# 20inputAND.net
KiCad netlist of a schematic drawn in EAGLE
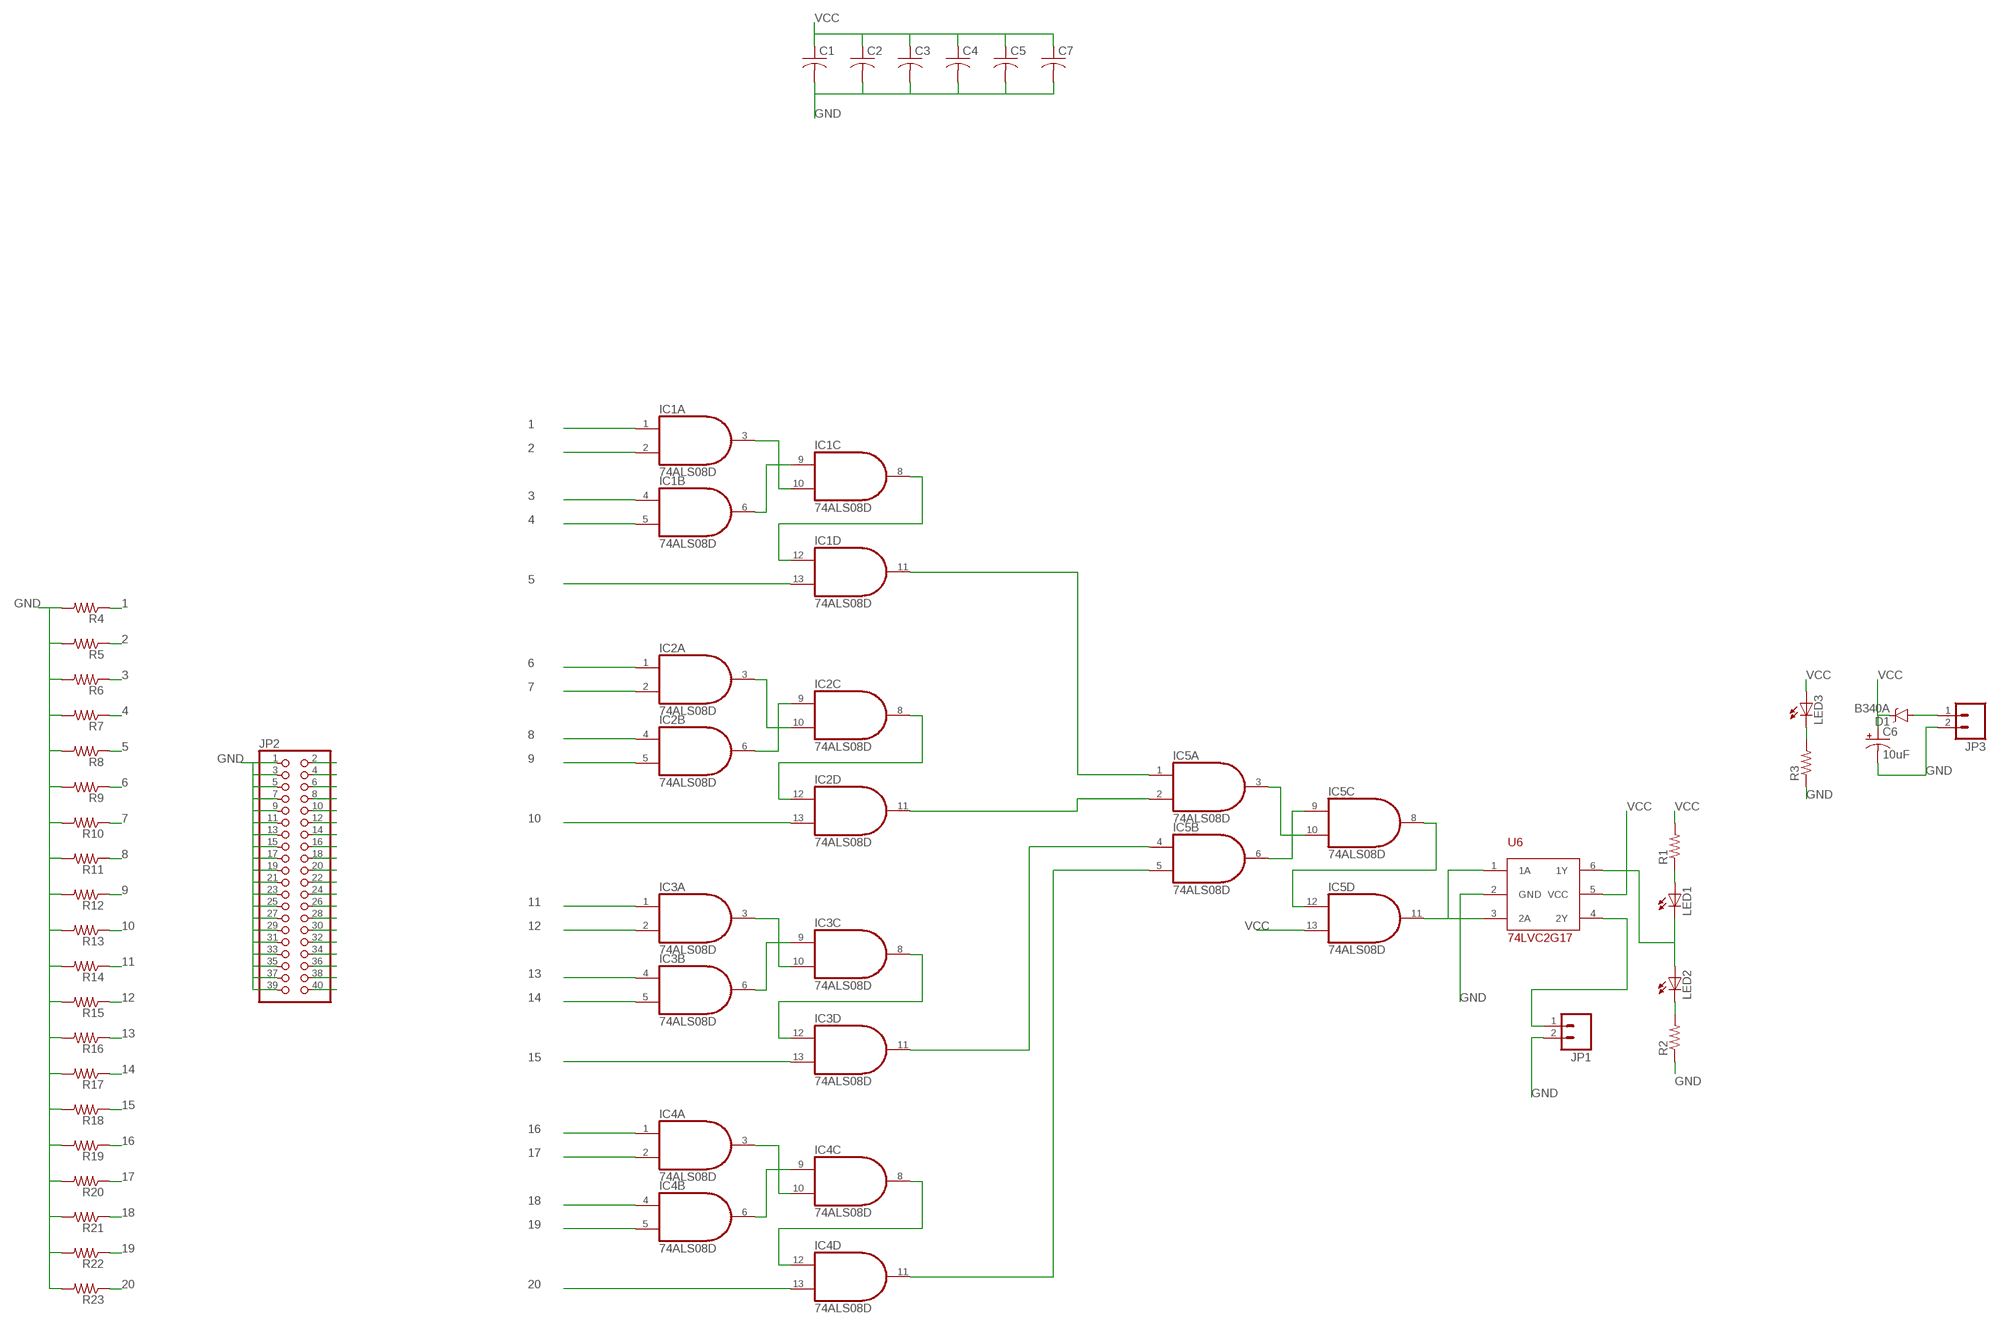
[diagram p0: schematic, sheet 1]

(export (version "E")
  (design (tool "Eeschema 10.0.6"))
  (components
    (comp (ref "C1")
      (value "C-USC0603")
      (footprint "eagle-import:C0603")
      (libsource (lib "eagle-import") (part "C-USC0603"))
    )
    (comp (ref "C2")
      (value "C-USC0603")
      (footprint "eagle-import:C0603")
      (libsource (lib "eagle-import") (part "C-USC0603"))
    )
    (comp (ref "C3")
      (value "C-USC0603")
      (footprint "eagle-import:C0603")
      (libsource (lib "eagle-import") (part "C-USC0603"))
    )
    (comp (ref "C4")
      (value "C-USC0603")
      (footprint "eagle-import:C0603")
      (libsource (lib "eagle-import") (part "C-USC0603"))
    )
    (comp (ref "C5")
      (value "C-USC0603")
      (footprint "eagle-import:C0603")
      (libsource (lib "eagle-import") (part "C-USC0603"))
    )
    (comp (ref "C6")
      (value "10uF")
      (footprint "eagle-import:EIA3216")
      (libsource (lib "eagle-import") (part "10UF-16V-10%(TANT)"))
    )
    (comp (ref "C7")
      (value "C-USC0603")
      (footprint "eagle-import:C0603")
      (libsource (lib "eagle-import") (part "C-USC0603"))
    )
    (comp (ref "D1")
      (value "B340A")
      (footprint "eagle-import:SMA-DIODE")
      (libsource (lib "eagle-import") (part "DIODE-SCHOTTKY-B340A"))
    )
    (comp (ref "IC1")
      (value "74ALS08D")
      (footprint "eagle-import:SO14")
      (libsource (lib "eagle-import") (part "7408DALS"))
    )
    (comp (ref "IC2")
      (value "74ALS08D")
      (footprint "eagle-import:SO14")
      (libsource (lib "eagle-import") (part "7408DALS"))
    )
    (comp (ref "IC3")
      (value "74ALS08D")
      (footprint "eagle-import:SO14")
      (libsource (lib "eagle-import") (part "7408DALS"))
    )
    (comp (ref "IC4")
      (value "74ALS08D")
      (footprint "eagle-import:SO14")
      (libsource (lib "eagle-import") (part "7408DALS"))
    )
    (comp (ref "IC5")
      (value "74ALS08D")
      (footprint "eagle-import:SO14")
      (libsource (lib "eagle-import") (part "7408DALS"))
    )
    (comp (ref "JP1")
      (value "M02PTH")
      (footprint "eagle-import:1X02")
      (libsource (lib "eagle-import") (part "M02PTH"))
    )
    (comp (ref "JP2")
      (value "PINHD-2X20")
      (footprint "eagle-import:2X20")
      (libsource (lib "eagle-import") (part "PINHD-2X20"))
    )
    (comp (ref "JP3")
      (value "M02PTH")
      (footprint "eagle-import:1X02")
      (libsource (lib "eagle-import") (part "M02PTH"))
    )
    (comp (ref "LED1")
      (value "LEDCHIPLED_1206")
      (footprint "eagle-import:CHIPLED_1206")
      (libsource (lib "eagle-import") (part "LEDCHIPLED_1206"))
    )
    (comp (ref "LED2")
      (value "LEDCHIPLED_1206")
      (footprint "eagle-import:CHIPLED_1206")
      (libsource (lib "eagle-import") (part "LEDCHIPLED_1206"))
    )
    (comp (ref "LED3")
      (value "LEDCHIPLED_0805")
      (footprint "eagle-import:CHIPLED_0805")
      (libsource (lib "eagle-import") (part "LEDCHIPLED_0805"))
    )
    (comp (ref "R1")
      (value "R-US_R0603")
      (footprint "eagle-import:R0603")
      (libsource (lib "eagle-import") (part "R-US_R0603"))
    )
    (comp (ref "R2")
      (value "R-US_R0603")
      (footprint "eagle-import:R0603")
      (libsource (lib "eagle-import") (part "R-US_R0603"))
    )
    (comp (ref "R3")
      (value "R-US_R0603")
      (footprint "eagle-import:R0603")
      (libsource (lib "eagle-import") (part "R-US_R0603"))
    )
    (comp (ref "R4")
      (value "R-US_R0603")
      (footprint "eagle-import:R0603")
      (libsource (lib "eagle-import") (part "R-US_R0603"))
    )
    (comp (ref "R5")
      (value "R-US_R0603")
      (footprint "eagle-import:R0603")
      (libsource (lib "eagle-import") (part "R-US_R0603"))
    )
    (comp (ref "R6")
      (value "R-US_R0603")
      (footprint "eagle-import:R0603")
      (libsource (lib "eagle-import") (part "R-US_R0603"))
    )
    (comp (ref "R7")
      (value "R-US_R0603")
      (footprint "eagle-import:R0603")
      (libsource (lib "eagle-import") (part "R-US_R0603"))
    )
    (comp (ref "R8")
      (value "R-US_R0603")
      (footprint "eagle-import:R0603")
      (libsource (lib "eagle-import") (part "R-US_R0603"))
    )
    (comp (ref "R9")
      (value "R-US_R0603")
      (footprint "eagle-import:R0603")
      (libsource (lib "eagle-import") (part "R-US_R0603"))
    )
    (comp (ref "R10")
      (value "R-US_R0603")
      (footprint "eagle-import:R0603")
      (libsource (lib "eagle-import") (part "R-US_R0603"))
    )
    (comp (ref "R11")
      (value "R-US_R0603")
      (footprint "eagle-import:R0603")
      (libsource (lib "eagle-import") (part "R-US_R0603"))
    )
    (comp (ref "R12")
      (value "R-US_R0603")
      (footprint "eagle-import:R0603")
      (libsource (lib "eagle-import") (part "R-US_R0603"))
    )
    (comp (ref "R13")
      (value "R-US_R0603")
      (footprint "eagle-import:R0603")
      (libsource (lib "eagle-import") (part "R-US_R0603"))
    )
    (comp (ref "R14")
      (value "R-US_R0603")
      (footprint "eagle-import:R0603")
      (libsource (lib "eagle-import") (part "R-US_R0603"))
    )
    (comp (ref "R15")
      (value "R-US_R0603")
      (footprint "eagle-import:R0603")
      (libsource (lib "eagle-import") (part "R-US_R0603"))
    )
    (comp (ref "R16")
      (value "R-US_R0603")
      (footprint "eagle-import:R0603")
      (libsource (lib "eagle-import") (part "R-US_R0603"))
    )
    (comp (ref "R17")
      (value "R-US_R0603")
      (footprint "eagle-import:R0603")
      (libsource (lib "eagle-import") (part "R-US_R0603"))
    )
    (comp (ref "R18")
      (value "R-US_R0603")
      (footprint "eagle-import:R0603")
      (libsource (lib "eagle-import") (part "R-US_R0603"))
    )
    (comp (ref "R19")
      (value "R-US_R0603")
      (footprint "eagle-import:R0603")
      (libsource (lib "eagle-import") (part "R-US_R0603"))
    )
    (comp (ref "R20")
      (value "R-US_R0603")
      (footprint "eagle-import:R0603")
      (libsource (lib "eagle-import") (part "R-US_R0603"))
    )
    (comp (ref "R21")
      (value "R-US_R0603")
      (footprint "eagle-import:R0603")
      (libsource (lib "eagle-import") (part "R-US_R0603"))
    )
    (comp (ref "R22")
      (value "R-US_R0603")
      (footprint "eagle-import:R0603")
      (libsource (lib "eagle-import") (part "R-US_R0603"))
    )
    (comp (ref "R23")
      (value "R-US_R0603")
      (footprint "eagle-import:R0603")
      (libsource (lib "eagle-import") (part "R-US_R0603"))
    )
    (comp (ref "U$2")
      (value "74LVC2G14/7")
      (footprint "eagle-import:SOT23-6")
      (libsource (lib "eagle-import") (part "74LVC2G14/7"))
    )
  )
  (nets
    (net (code "1") (name "/1") (class "Default")
      (node (ref "IC1") (pin "1") (pinfunction "I0_1") (pintype "input"))
      (node (ref "JP2") (pin "2") (pinfunction "2_2") (pintype "passive"))
      (node (ref "R4") (pin "1") (pinfunction "1_1") (pintype "passive"))
    )
    (net (code "2") (name "/2") (class "Default")
      (node (ref "IC1") (pin "2") (pinfunction "I1_2") (pintype "input"))
      (node (ref "JP2") (pin "4") (pinfunction "4_4") (pintype "passive"))
      (node (ref "R5") (pin "1") (pinfunction "1_1") (pintype "passive"))
    )
    (net (code "3") (name "/3") (class "Default")
      (node (ref "IC1") (pin "4") (pinfunction "I0_4") (pintype "input"))
      (node (ref "JP2") (pin "6") (pinfunction "6_6") (pintype "passive"))
      (node (ref "R6") (pin "1") (pinfunction "1_1") (pintype "passive"))
    )
    (net (code "4") (name "/4") (class "Default")
      (node (ref "IC1") (pin "5") (pinfunction "I1_5") (pintype "input"))
      (node (ref "JP2") (pin "8") (pinfunction "8_8") (pintype "passive"))
      (node (ref "R7") (pin "1") (pinfunction "1_1") (pintype "passive"))
    )
    (net (code "5") (name "/5") (class "Default")
      (node (ref "IC1") (pin "13") (pinfunction "I1_13") (pintype "input"))
      (node (ref "JP2") (pin "10") (pinfunction "10_10") (pintype "passive"))
      (node (ref "R8") (pin "1") (pinfunction "1_1") (pintype "passive"))
    )
    (net (code "6") (name "/6") (class "Default")
      (node (ref "IC2") (pin "1") (pinfunction "I0_1") (pintype "input"))
      (node (ref "JP2") (pin "12") (pinfunction "12_12") (pintype "passive"))
      (node (ref "R9") (pin "1") (pinfunction "1_1") (pintype "passive"))
    )
    (net (code "7") (name "/7") (class "Default")
      (node (ref "IC2") (pin "2") (pinfunction "I1_2") (pintype "input"))
      (node (ref "JP2") (pin "14") (pinfunction "14_14") (pintype "passive"))
      (node (ref "R10") (pin "1") (pinfunction "1_1") (pintype "passive"))
    )
    (net (code "8") (name "/8") (class "Default")
      (node (ref "IC2") (pin "4") (pinfunction "I0_4") (pintype "input"))
      (node (ref "JP2") (pin "16") (pinfunction "16_16") (pintype "passive"))
      (node (ref "R11") (pin "1") (pinfunction "1_1") (pintype "passive"))
    )
    (net (code "9") (name "/9") (class "Default")
      (node (ref "IC2") (pin "5") (pinfunction "I1_5") (pintype "input"))
      (node (ref "JP2") (pin "18") (pinfunction "18_18") (pintype "passive"))
      (node (ref "R12") (pin "1") (pinfunction "1_1") (pintype "passive"))
    )
    (net (code "10") (name "/10") (class "Default")
      (node (ref "IC2") (pin "13") (pinfunction "I1_13") (pintype "input"))
      (node (ref "JP2") (pin "20") (pinfunction "20_20") (pintype "passive"))
      (node (ref "R13") (pin "1") (pinfunction "1_1") (pintype "passive"))
    )
    (net (code "11") (name "/11") (class "Default")
      (node (ref "IC3") (pin "1") (pinfunction "I0_1") (pintype "input"))
      (node (ref "JP2") (pin "22") (pinfunction "22_22") (pintype "passive"))
      (node (ref "R14") (pin "1") (pinfunction "1_1") (pintype "passive"))
    )
    (net (code "12") (name "/12") (class "Default")
      (node (ref "IC3") (pin "2") (pinfunction "I1_2") (pintype "input"))
      (node (ref "JP2") (pin "24") (pinfunction "24_24") (pintype "passive"))
      (node (ref "R15") (pin "1") (pinfunction "1_1") (pintype "passive"))
    )
    (net (code "13") (name "/13") (class "Default")
      (node (ref "IC3") (pin "4") (pinfunction "I0_4") (pintype "input"))
      (node (ref "JP2") (pin "26") (pinfunction "26_26") (pintype "passive"))
      (node (ref "R16") (pin "1") (pinfunction "1_1") (pintype "passive"))
    )
    (net (code "14") (name "/14") (class "Default")
      (node (ref "IC3") (pin "5") (pinfunction "I1_5") (pintype "input"))
      (node (ref "JP2") (pin "28") (pinfunction "28_28") (pintype "passive"))
      (node (ref "R17") (pin "1") (pinfunction "1_1") (pintype "passive"))
    )
    (net (code "15") (name "/15") (class "Default")
      (node (ref "IC3") (pin "13") (pinfunction "I1_13") (pintype "input"))
      (node (ref "JP2") (pin "30") (pinfunction "30_30") (pintype "passive"))
      (node (ref "R18") (pin "1") (pinfunction "1_1") (pintype "passive"))
    )
    (net (code "16") (name "/16") (class "Default")
      (node (ref "IC4") (pin "1") (pinfunction "I0_1") (pintype "input"))
      (node (ref "JP2") (pin "32") (pinfunction "32_32") (pintype "passive"))
      (node (ref "R19") (pin "1") (pinfunction "1_1") (pintype "passive"))
    )
    (net (code "17") (name "/17") (class "Default")
      (node (ref "IC4") (pin "2") (pinfunction "I1_2") (pintype "input"))
      (node (ref "JP2") (pin "34") (pinfunction "34_34") (pintype "passive"))
      (node (ref "R20") (pin "1") (pinfunction "1_1") (pintype "passive"))
    )
    (net (code "18") (name "/18") (class "Default")
      (node (ref "IC4") (pin "4") (pinfunction "I0_4") (pintype "input"))
      (node (ref "JP2") (pin "36") (pinfunction "36_36") (pintype "passive"))
      (node (ref "R21") (pin "1") (pinfunction "1_1") (pintype "passive"))
    )
    (net (code "19") (name "/19") (class "Default")
      (node (ref "IC4") (pin "5") (pinfunction "I1_5") (pintype "input"))
      (node (ref "JP2") (pin "38") (pinfunction "38_38") (pintype "passive"))
      (node (ref "R22") (pin "1") (pinfunction "1_1") (pintype "passive"))
    )
    (net (code "20") (name "/20") (class "Default")
      (node (ref "IC4") (pin "13") (pinfunction "I1_13") (pintype "input"))
      (node (ref "JP2") (pin "40") (pinfunction "40_40") (pintype "passive"))
      (node (ref "R23") (pin "1") (pinfunction "1_1") (pintype "passive"))
    )
    (net (code "21") (name "/GND") (class "Default")
      (node (ref "C1") (pin "2") (pinfunction "2_2") (pintype "passive"))
      (node (ref "C2") (pin "2") (pinfunction "2_2") (pintype "passive"))
      (node (ref "C3") (pin "2") (pinfunction "2_2") (pintype "passive"))
      (node (ref "C4") (pin "2") (pinfunction "2_2") (pintype "passive"))
      (node (ref "C5") (pin "2") (pinfunction "2_2") (pintype "passive"))
      (node (ref "C6") (pin "C") (pinfunction "-_C") (pintype "passive"))
      (node (ref "C7") (pin "2") (pinfunction "2_2") (pintype "passive"))
      (node (ref "JP1") (pin "2") (pinfunction "2_2") (pintype "passive"))
      (node (ref "JP2") (pin "1") (pinfunction "1_1") (pintype "passive"))
      (node (ref "JP2") (pin "11") (pinfunction "11_11") (pintype "passive"))
      (node (ref "JP2") (pin "13") (pinfunction "13_13") (pintype "passive"))
      (node (ref "JP2") (pin "15") (pinfunction "15_15") (pintype "passive"))
      (node (ref "JP2") (pin "17") (pinfunction "17_17") (pintype "passive"))
      (node (ref "JP2") (pin "19") (pinfunction "19_19") (pintype "passive"))
      (node (ref "JP2") (pin "21") (pinfunction "21_21") (pintype "passive"))
      (node (ref "JP2") (pin "23") (pinfunction "23_23") (pintype "passive"))
      (node (ref "JP2") (pin "25") (pinfunction "25_25") (pintype "passive"))
      (node (ref "JP2") (pin "27") (pinfunction "27_27") (pintype "passive"))
      (node (ref "JP2") (pin "29") (pinfunction "29_29") (pintype "passive"))
      (node (ref "JP2") (pin "3") (pinfunction "3_3") (pintype "passive"))
      (node (ref "JP2") (pin "31") (pinfunction "31_31") (pintype "passive"))
      (node (ref "JP2") (pin "33") (pinfunction "33_33") (pintype "passive"))
      (node (ref "JP2") (pin "35") (pinfunction "35_35") (pintype "passive"))
      (node (ref "JP2") (pin "37") (pinfunction "37_37") (pintype "passive"))
      (node (ref "JP2") (pin "39") (pinfunction "39_39") (pintype "passive"))
      (node (ref "JP2") (pin "5") (pinfunction "5_5") (pintype "passive"))
      (node (ref "JP2") (pin "7") (pinfunction "7_7") (pintype "passive"))
      (node (ref "JP2") (pin "9") (pinfunction "9_9") (pintype "passive"))
      (node (ref "JP3") (pin "2") (pinfunction "2_2") (pintype "passive"))
      (node (ref "R10") (pin "2") (pinfunction "2_2") (pintype "passive"))
      (node (ref "R11") (pin "2") (pinfunction "2_2") (pintype "passive"))
      (node (ref "R12") (pin "2") (pinfunction "2_2") (pintype "passive"))
      (node (ref "R13") (pin "2") (pinfunction "2_2") (pintype "passive"))
      (node (ref "R14") (pin "2") (pinfunction "2_2") (pintype "passive"))
      (node (ref "R15") (pin "2") (pinfunction "2_2") (pintype "passive"))
      (node (ref "R16") (pin "2") (pinfunction "2_2") (pintype "passive"))
      (node (ref "R17") (pin "2") (pinfunction "2_2") (pintype "passive"))
      (node (ref "R18") (pin "2") (pinfunction "2_2") (pintype "passive"))
      (node (ref "R19") (pin "2") (pinfunction "2_2") (pintype "passive"))
      (node (ref "R2") (pin "1") (pinfunction "1_1") (pintype "passive"))
      (node (ref "R20") (pin "2") (pinfunction "2_2") (pintype "passive"))
      (node (ref "R21") (pin "2") (pinfunction "2_2") (pintype "passive"))
      (node (ref "R22") (pin "2") (pinfunction "2_2") (pintype "passive"))
      (node (ref "R23") (pin "2") (pinfunction "2_2") (pintype "passive"))
      (node (ref "R3") (pin "1") (pinfunction "1_1") (pintype "passive"))
      (node (ref "R4") (pin "2") (pinfunction "2_2") (pintype "passive"))
      (node (ref "R5") (pin "2") (pinfunction "2_2") (pintype "passive"))
      (node (ref "R6") (pin "2") (pinfunction "2_2") (pintype "passive"))
      (node (ref "R7") (pin "2") (pinfunction "2_2") (pintype "passive"))
      (node (ref "R8") (pin "2") (pinfunction "2_2") (pintype "passive"))
      (node (ref "R9") (pin "2") (pinfunction "2_2") (pintype "passive"))
      (node (ref "U$2") (pin "2") (pinfunction "GND_2") (pintype "bidirectional"))
    )
    (net (code "22") (name "/VCC") (class "Default")
      (node (ref "C1") (pin "1") (pinfunction "1_1") (pintype "passive"))
      (node (ref "C2") (pin "1") (pinfunction "1_1") (pintype "passive"))
      (node (ref "C3") (pin "1") (pinfunction "1_1") (pintype "passive"))
      (node (ref "C4") (pin "1") (pinfunction "1_1") (pintype "passive"))
      (node (ref "C5") (pin "1") (pinfunction "1_1") (pintype "passive"))
      (node (ref "C6") (pin "A") (pinfunction "+_A") (pintype "passive"))
      (node (ref "C7") (pin "1") (pinfunction "1_1") (pintype "passive"))
      (node (ref "D1") (pin "C") (pinfunction "C_C") (pintype "passive"))
      (node (ref "IC5") (pin "13") (pinfunction "I1_13") (pintype "input"))
      (node (ref "LED3") (pin "A") (pinfunction "A_A") (pintype "passive"))
      (node (ref "R1") (pin "2") (pinfunction "2_2") (pintype "passive"))
      (node (ref "U$2") (pin "5") (pinfunction "VCC_5") (pintype "bidirectional"))
    )
    (net (code "23") (name "Net-(D1-PadA)") (class "Default")
      (node (ref "D1") (pin "A") (pinfunction "A_A") (pintype "passive"))
      (node (ref "JP3") (pin "1") (pinfunction "1_1") (pintype "passive"))
    )
    (net (code "24") (name "Net-(IC1A-O)") (class "Default")
      (node (ref "IC1") (pin "10") (pinfunction "I1_10") (pintype "input"))
      (node (ref "IC1") (pin "3") (pinfunction "O_3") (pintype "output"))
    )
    (net (code "25") (name "Net-(IC1B-O)") (class "Default")
      (node (ref "IC1") (pin "6") (pinfunction "O_6") (pintype "output"))
      (node (ref "IC1") (pin "9") (pinfunction "I0_9") (pintype "input"))
    )
    (net (code "26") (name "Net-(IC1C-O)") (class "Default")
      (node (ref "IC1") (pin "12") (pinfunction "I0_12") (pintype "input"))
      (node (ref "IC1") (pin "8") (pinfunction "O_8") (pintype "output"))
    )
    (net (code "27") (name "Net-(IC1D-O)") (class "Default")
      (node (ref "IC1") (pin "11") (pinfunction "O_11") (pintype "output"))
      (node (ref "IC5") (pin "1") (pinfunction "I0_1") (pintype "input"))
    )
    (net (code "28") (name "Net-(IC2A-O)") (class "Default")
      (node (ref "IC2") (pin "10") (pinfunction "I1_10") (pintype "input"))
      (node (ref "IC2") (pin "3") (pinfunction "O_3") (pintype "output"))
    )
    (net (code "29") (name "Net-(IC2B-O)") (class "Default")
      (node (ref "IC2") (pin "6") (pinfunction "O_6") (pintype "output"))
      (node (ref "IC2") (pin "9") (pinfunction "I0_9") (pintype "input"))
    )
    (net (code "30") (name "Net-(IC2C-O)") (class "Default")
      (node (ref "IC2") (pin "12") (pinfunction "I0_12") (pintype "input"))
      (node (ref "IC2") (pin "8") (pinfunction "O_8") (pintype "output"))
    )
    (net (code "31") (name "Net-(IC2D-O)") (class "Default")
      (node (ref "IC2") (pin "11") (pinfunction "O_11") (pintype "output"))
      (node (ref "IC5") (pin "2") (pinfunction "I1_2") (pintype "input"))
    )
    (net (code "32") (name "Net-(IC3A-O)") (class "Default")
      (node (ref "IC3") (pin "10") (pinfunction "I1_10") (pintype "input"))
      (node (ref "IC3") (pin "3") (pinfunction "O_3") (pintype "output"))
    )
    (net (code "33") (name "Net-(IC3B-O)") (class "Default")
      (node (ref "IC3") (pin "6") (pinfunction "O_6") (pintype "output"))
      (node (ref "IC3") (pin "9") (pinfunction "I0_9") (pintype "input"))
    )
    (net (code "34") (name "Net-(IC3C-O)") (class "Default")
      (node (ref "IC3") (pin "12") (pinfunction "I0_12") (pintype "input"))
      (node (ref "IC3") (pin "8") (pinfunction "O_8") (pintype "output"))
    )
    (net (code "35") (name "Net-(IC3D-O)") (class "Default")
      (node (ref "IC3") (pin "11") (pinfunction "O_11") (pintype "output"))
      (node (ref "IC5") (pin "4") (pinfunction "I0_4") (pintype "input"))
    )
    (net (code "36") (name "Net-(IC4A-O)") (class "Default")
      (node (ref "IC4") (pin "10") (pinfunction "I1_10") (pintype "input"))
      (node (ref "IC4") (pin "3") (pinfunction "O_3") (pintype "output"))
    )
    (net (code "37") (name "Net-(IC4B-O)") (class "Default")
      (node (ref "IC4") (pin "6") (pinfunction "O_6") (pintype "output"))
      (node (ref "IC4") (pin "9") (pinfunction "I0_9") (pintype "input"))
    )
    (net (code "38") (name "Net-(IC4C-O)") (class "Default")
      (node (ref "IC4") (pin "12") (pinfunction "I0_12") (pintype "input"))
      (node (ref "IC4") (pin "8") (pinfunction "O_8") (pintype "output"))
    )
    (net (code "39") (name "Net-(IC4D-O)") (class "Default")
      (node (ref "IC4") (pin "11") (pinfunction "O_11") (pintype "output"))
      (node (ref "IC5") (pin "5") (pinfunction "I1_5") (pintype "input"))
    )
    (net (code "40") (name "Net-(IC5A-O)") (class "Default")
      (node (ref "IC5") (pin "10") (pinfunction "I1_10") (pintype "input"))
      (node (ref "IC5") (pin "3") (pinfunction "O_3") (pintype "output"))
    )
    (net (code "41") (name "Net-(IC5B-O)") (class "Default")
      (node (ref "IC5") (pin "6") (pinfunction "O_6") (pintype "output"))
      (node (ref "IC5") (pin "9") (pinfunction "I0_9") (pintype "input"))
    )
    (net (code "42") (name "Net-(IC5C-O)") (class "Default")
      (node (ref "IC5") (pin "12") (pinfunction "I0_12") (pintype "input"))
      (node (ref "IC5") (pin "8") (pinfunction "O_8") (pintype "output"))
    )
    (net (code "43") (name "Net-(IC5D-O)") (class "Default")
      (node (ref "IC5") (pin "11") (pinfunction "O_11") (pintype "output"))
      (node (ref "U$2") (pin "1") (pinfunction "1A_1") (pintype "bidirectional"))
      (node (ref "U$2") (pin "3") (pinfunction "2A_3") (pintype "bidirectional"))
    )
    (net (code "44") (name "Net-(LED1-PadA)") (class "Default")
      (node (ref "LED1") (pin "A") (pinfunction "A_A") (pintype "passive"))
      (node (ref "R1") (pin "1") (pinfunction "1_1") (pintype "passive"))
    )
    (net (code "45") (name "Net-(LED2-PadC)") (class "Default")
      (node (ref "LED2") (pin "C") (pinfunction "C_C") (pintype "passive"))
      (node (ref "R2") (pin "2") (pinfunction "2_2") (pintype "passive"))
    )
    (net (code "46") (name "Net-(LED3-PadC)") (class "Default")
      (node (ref "LED3") (pin "C") (pinfunction "C_C") (pintype "passive"))
      (node (ref "R3") (pin "2") (pinfunction "2_2") (pintype "passive"))
    )
    (net (code "47") (name "Net-(U$2-1Y)") (class "Default")
      (node (ref "LED1") (pin "C") (pinfunction "C_C") (pintype "passive"))
      (node (ref "LED2") (pin "A") (pinfunction "A_A") (pintype "passive"))
      (node (ref "U$2") (pin "6") (pinfunction "1Y_6") (pintype "bidirectional"))
    )
    (net (code "48") (name "Net-(U$2-2Y)") (class "Default")
      (node (ref "JP1") (pin "1") (pinfunction "1_1") (pintype "passive"))
      (node (ref "U$2") (pin "4") (pinfunction "2Y_4") (pintype "bidirectional"))
    )
  )
)
